# u1_heater_control.net
KiCad netlist of a schematic drawn in Altium Designer
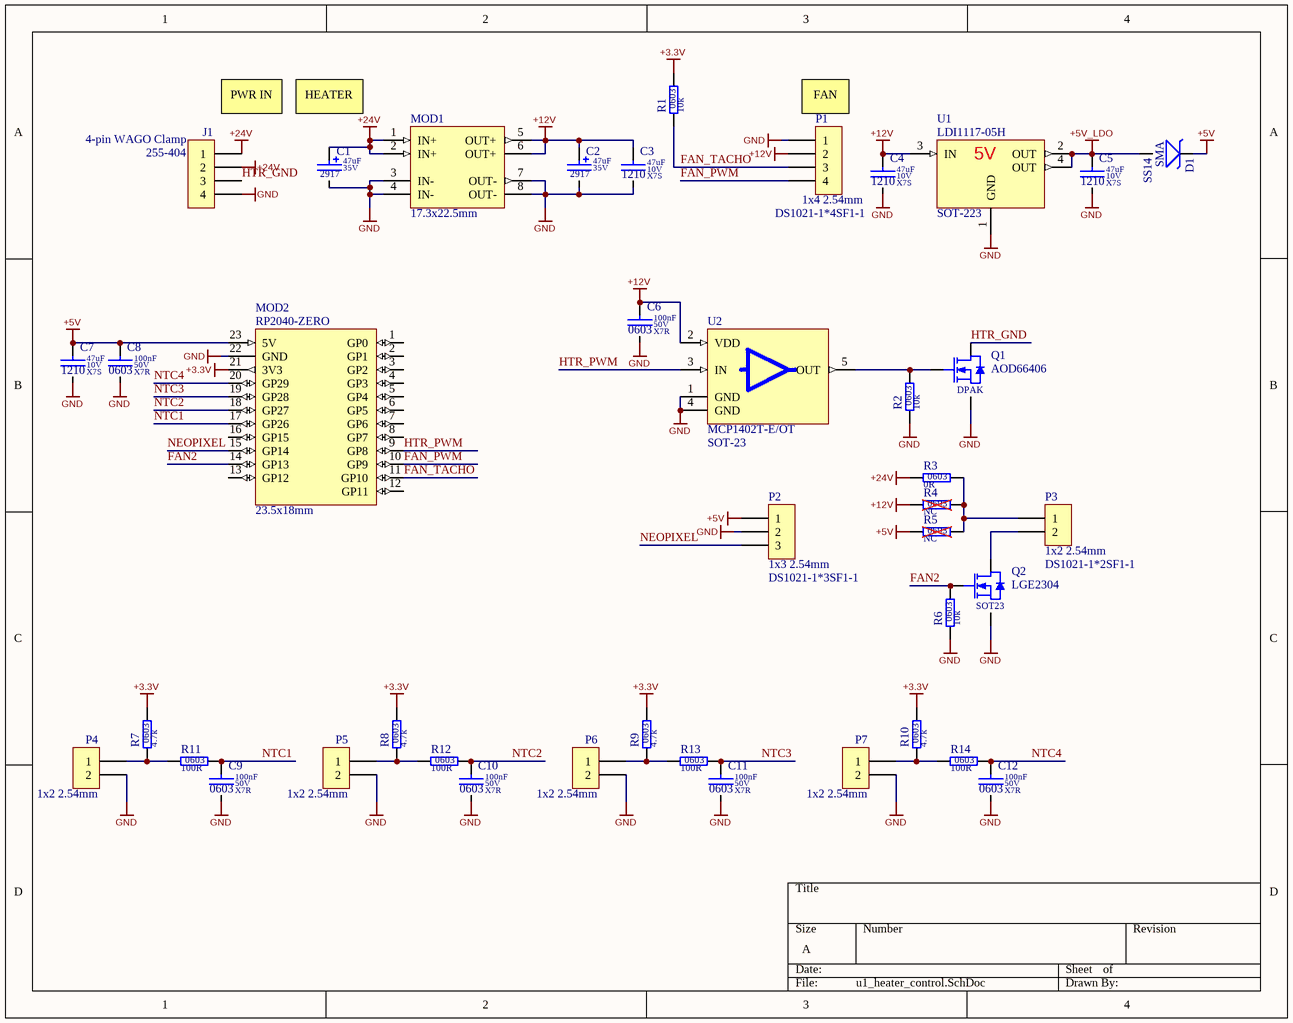
[diagram p0: u1_heater_control.SchDoc]

(export (version "E")
  (design (tool "Eeschema 10.0.6"))
  (components
    (comp (ref "C1")
      (value "47uF")
      (footprint "CT_2917_7343")
      (description "Capacitor")
      (fields
        (field (name "SCH_FOOTPRINT") "2917")
        (field (name "VOLTAGE") "35V")
        (field (name "PART NUMBER") "CT_47uF_35V_TA2O5_2917_20_T541")
        (field (name "MANUFACTURER") "Kemet")
      )
      (libsource (lib "Library") (part "CT"))
    )
    (comp (ref "C2")
      (value "47uF")
      (footprint "CT_2917_7343")
      (description "Capacitor")
      (fields
        (field (name "SCH_FOOTPRINT") "2917")
        (field (name "VOLTAGE") "35V")
        (field (name "PART NUMBER") "CT_47uF_35V_TA2O5_2917_20_T541")
        (field (name "MANUFACTURER") "Kemet")
      )
      (libsource (lib "Library") (part "CT"))
    )
    (comp (ref "C3")
      (value "47uF")
      (footprint "C_1210_3225")
      (description "Capacitor")
      (fields
        (field (name "DIELECTRIC") "X7S")
        (field (name "VOLTAGE") "10V")
        (field (name "SCH_FOOTPRINT") "1210")
        (field (name "PART NUMBER") "C_47uF_10V_X7S_1210_10_AECQ1")
        (field (name "MANUFACTURER") "Murata")
      )
      (libsource (lib "Library") (part "C"))
    )
    (comp (ref "C4")
      (value "47uF")
      (footprint "C_1210_3225")
      (description "Capacitor")
      (fields
        (field (name "DIELECTRIC") "X7S")
        (field (name "VOLTAGE") "10V")
        (field (name "SCH_FOOTPRINT") "1210")
        (field (name "PART NUMBER") "C_47uF_10V_X7S_1210_10_AECQ1")
        (field (name "MANUFACTURER") "Murata")
      )
      (libsource (lib "Library") (part "C"))
    )
    (comp (ref "C5")
      (value "47uF")
      (footprint "C_1210_3225")
      (description "Capacitor")
      (fields
        (field (name "DIELECTRIC") "X7S")
        (field (name "VOLTAGE") "10V")
        (field (name "SCH_FOOTPRINT") "1210")
        (field (name "PART NUMBER") "C_47uF_10V_X7S_1210_10_AECQ1")
        (field (name "MANUFACTURER") "Murata")
      )
      (libsource (lib "Library") (part "C"))
    )
    (comp (ref "C6")
      (value "100nF")
      (footprint "C_0603_1608")
      (description "Capacitor")
      (fields
        (field (name "DIELECTRIC") "X7R")
        (field (name "VOLTAGE") "50V")
        (field (name "SCH_FOOTPRINT") "0603")
        (field (name "PART NUMBER") "C_100nF_50V_X7R_0603_5")
        (field (name "MANUFACTURER") "Samsung")
      )
      (libsource (lib "Library") (part "C"))
    )
    (comp (ref "C7")
      (value "47uF")
      (footprint "C_1210_3225")
      (description "Capacitor")
      (fields
        (field (name "DIELECTRIC") "X7S")
        (field (name "VOLTAGE") "10V")
        (field (name "SCH_FOOTPRINT") "1210")
        (field (name "PART NUMBER") "C_47uF_10V_X7S_1210_10_AECQ1")
        (field (name "MANUFACTURER") "Murata")
      )
      (libsource (lib "Library") (part "C"))
    )
    (comp (ref "C8")
      (value "100nF")
      (footprint "C_0603_1608")
      (description "Capacitor")
      (fields
        (field (name "DIELECTRIC") "X7R")
        (field (name "VOLTAGE") "50V")
        (field (name "SCH_FOOTPRINT") "0603")
        (field (name "PART NUMBER") "C_100nF_50V_X7R_0603_5")
        (field (name "MANUFACTURER") "Samsung")
      )
      (libsource (lib "Library") (part "C"))
    )
    (comp (ref "C9")
      (value "100nF")
      (footprint "C_0603_1608")
      (description "Capacitor")
      (fields
        (field (name "DIELECTRIC") "X7R")
        (field (name "VOLTAGE") "50V")
        (field (name "SCH_FOOTPRINT") "0603")
        (field (name "PART NUMBER") "C_100nF_50V_X7R_0603_5")
        (field (name "MANUFACTURER") "Samsung")
      )
      (libsource (lib "Library") (part "C"))
    )
    (comp (ref "C10")
      (value "100nF")
      (footprint "C_0603_1608")
      (description "Capacitor")
      (fields
        (field (name "DIELECTRIC") "X7R")
        (field (name "VOLTAGE") "50V")
        (field (name "SCH_FOOTPRINT") "0603")
        (field (name "PART NUMBER") "C_100nF_50V_X7R_0603_5")
        (field (name "MANUFACTURER") "Samsung")
      )
      (libsource (lib "Library") (part "C"))
    )
    (comp (ref "C11")
      (value "100nF")
      (footprint "C_0603_1608")
      (description "Capacitor")
      (fields
        (field (name "DIELECTRIC") "X7R")
        (field (name "VOLTAGE") "50V")
        (field (name "SCH_FOOTPRINT") "0603")
        (field (name "PART NUMBER") "C_100nF_50V_X7R_0603_5")
        (field (name "MANUFACTURER") "Samsung")
      )
      (libsource (lib "Library") (part "C"))
    )
    (comp (ref "C12")
      (value "100nF")
      (footprint "C_0603_1608")
      (description "Capacitor")
      (fields
        (field (name "DIELECTRIC") "X7R")
        (field (name "VOLTAGE") "50V")
        (field (name "SCH_FOOTPRINT") "0603")
        (field (name "PART NUMBER") "C_100nF_50V_X7R_0603_5")
        (field (name "MANUFACTURER") "Samsung")
      )
      (libsource (lib "Library") (part "C"))
    )
    (comp (ref "D1")
      (value "SS14")
      (footprint "SMA_DO-214AC")
      (fields
        (field (name "SCH_FOOTPRINT") "SMA")
        (field (name "PART NUMBER") "DS_SS14_1A_40V_SMA")
        (field (name "VOLTAGE") "40V")
        (field (name "MANUFACTURER") "ON Semiconductor")
      )
      (libsource (lib "Library") (part "DS"))
    )
    (comp (ref "J1")
      (value "255-404")
      (footprint "J_255-404")
      (description "Pin Header")
      (fields
        (field (name "SCH_FOOTPRINT") "4-pin WAGO Clamp")
        (field (name "PART NUMBER") "J_255-404")
        (field (name "MANUFACTURER") "Wago")
      )
      (libsource (lib "Library") (part "J_HEADER_1x4"))
    )
    (comp (ref "MOD1")
      (value "Low cost, Aliexpress-ready DC-DC buck converter using MP1584")
      (footprint "MOD_BUCK_MP1584")
      (fields (field (name "SCH_FOOTPRINT") "17.3x22.5mm") (field (name "PART NUMBER") "MOD_BUCK_MP1584"))
      (libsource (lib "Library") (part "MOD_BUCK_MP1584"))
    )
    (comp (ref "MOD2")
      (value "RP2040-ZERO")
      (footprint "MOD_RP2040-ZERO")
      (fields
        (field (name "SCH_FOOTPRINT") "23.5x18mm")
        (field (name "PART NUMBER") "MOD_RP2040-ZERO")
        (field (name "MANUFACTURER") "Waveshare")
        (field (name "Comment") "RP2040 module")
      )
      (libsource (lib "Library") (part "MOD_RP2040-ZERO"))
    )
    (comp (ref "P1")
      (value "DS1021-1*4SF1-1")
      (footprint "P_HEADER_1x4_2.54")
      (description "Pin Header")
      (fields
        (field (name "SCH_FOOTPRINT") "1x4 2.54mm")
        (field (name "PART NUMBER") "P_HEADER_1x4_2.54")
        (field (name "MANUFACTURER") "Connfly")
      )
      (libsource (lib "Library") (part "P_HEADER_1x4"))
    )
    (comp (ref "P2")
      (value "DS1021-1*3SF1-1")
      (footprint "P_HEADER_1x3_2.54")
      (description "Pin Header")
      (fields
        (field (name "SCH_FOOTPRINT") "1x3 2.54mm")
        (field (name "PART NUMBER") "P_HEADER_1x3_2.54")
        (field (name "MANUFACTURER") "Connfly")
      )
      (libsource (lib "Library") (part "P_HEADER_1x3"))
    )
    (comp (ref "P3")
      (value "DS1021-1*2SF1-1")
      (footprint "P_HEADER_1x2_2.54")
      (description "Pin Header")
      (fields
        (field (name "SCH_FOOTPRINT") "1x2 2.54mm")
        (field (name "PART NUMBER") "P_HEADER_1x2_2.54")
        (field (name "MANUFACTURER") "Connfly")
      )
      (libsource (lib "") (part "P_HEADER_1x2_1"))
    )
    (comp (ref "P4")
      (value "Goldpin")
      (footprint "P_HEADER_1x2_2.54")
      (description "Pin Header")
      (fields
        (field (name "SCH_FOOTPRINT") "1x2 2.54mm")
        (field (name "PART NUMBER") "P_HEADER_1x2_2.54")
        (field (name "MANUFACTURER") "Connfly")
      )
      (libsource (lib "Library") (part "P_HEADER_1x2"))
    )
    (comp (ref "P5")
      (value "Goldpin")
      (footprint "P_HEADER_1x2_2.54")
      (description "Pin Header")
      (fields
        (field (name "SCH_FOOTPRINT") "1x2 2.54mm")
        (field (name "PART NUMBER") "P_HEADER_1x2_2.54")
        (field (name "MANUFACTURER") "Connfly")
      )
      (libsource (lib "Library") (part "P_HEADER_1x2"))
    )
    (comp (ref "P6")
      (value "Goldpin")
      (footprint "P_HEADER_1x2_2.54")
      (description "Pin Header")
      (fields
        (field (name "SCH_FOOTPRINT") "1x2 2.54mm")
        (field (name "PART NUMBER") "P_HEADER_1x2_2.54")
        (field (name "MANUFACTURER") "Connfly")
      )
      (libsource (lib "Library") (part "P_HEADER_1x2"))
    )
    (comp (ref "P7")
      (value "Goldpin")
      (footprint "P_HEADER_1x2_2.54")
      (description "Pin Header")
      (fields
        (field (name "SCH_FOOTPRINT") "1x2 2.54mm")
        (field (name "PART NUMBER") "P_HEADER_1x2_2.54")
        (field (name "MANUFACTURER") "Connfly")
      )
      (libsource (lib "Library") (part "P_HEADER_1x2"))
    )
    (comp (ref "Q1")
      (value "AOD66406")
      (footprint "DPAK_TO252-3_SC63_M")
      (fields
        (field (name "SCH_FOOTPRINT") "DPAK")
        (field (name "PART NUMBER") "QN_AOD66406")
        (field (name "VOLTAGE") "40V")
        (field (name "MANUFACTURER") "Alpha&Omega Semiconductor")
      )
      (libsource (lib "Library") (part "QN_GDS"))
    )
    (comp (ref "Q2")
      (value "LGE2304")
      (footprint "SOT23_TO236_SC59")
      (fields
        (field (name "SCH_FOOTPRINT") "SOT23")
        (field (name "PART NUMBER") "QN_LGE2304")
        (field (name "VOLTAGE") "30V")
        (field (name "MANUFACTURER") "Luguang Electronic Technology")
      )
      (libsource (lib "Library") (part "QN_GSD"))
    )
    (comp (ref "R1")
      (value "10k")
      (footprint "R_0603_1608")
      (fields
        (field (name "SCH_FOOTPRINT") "0603")
        (field (name "PART NUMBER") "R_10k_0603_1_AECQ0")
        (field (name "VOLTAGE") "75V")
        (field (name "POWER") "100mW")
      )
      (libsource (lib "Library") (part "R"))
    )
    (comp (ref "R2")
      (value "10k")
      (footprint "R_0603_1608")
      (fields
        (field (name "SCH_FOOTPRINT") "0603")
        (field (name "PART NUMBER") "R_10k_0603_1_AECQ0")
        (field (name "VOLTAGE") "75V")
        (field (name "POWER") "100mW")
      )
      (libsource (lib "Library") (part "R"))
    )
    (comp (ref "R3")
      (value "0R")
      (footprint "R_0603_1608")
      (fields
        (field (name "SCH_FOOTPRINT") "0603")
        (field (name "PART NUMBER") "R_0R_0603_1")
        (field (name "VOLTAGE") "75V")
        (field (name "POWER") "100mW")
      )
      (libsource (lib "Library") (part "R"))
    )
    (comp (ref "R4")
      (value "NC")
      (footprint "R_NC_0603_1608")
      (fields
        (field (name "SCH_FOOTPRINT") "0603")
        (field (name "PART NUMBER") "R_GENERIC_0603")
        (field (name "Comment") "Resistor")
      )
      (libsource (lib "Library") (part "R_NC"))
    )
    (comp (ref "R5")
      (value "NC")
      (footprint "R_NC_0603_1608")
      (fields
        (field (name "SCH_FOOTPRINT") "0603")
        (field (name "PART NUMBER") "R_GENERIC_0603")
        (field (name "Comment") "Resistor")
      )
      (libsource (lib "Library") (part "R_NC"))
    )
    (comp (ref "R6")
      (value "10k")
      (footprint "R_0603_1608")
      (fields
        (field (name "SCH_FOOTPRINT") "0603")
        (field (name "PART NUMBER") "R_10k_0603_1_AECQ0")
        (field (name "VOLTAGE") "75V")
        (field (name "POWER") "100mW")
      )
      (libsource (lib "Library") (part "R"))
    )
    (comp (ref "R7")
      (value "4.7k")
      (footprint "R_0603_1608")
      (fields
        (field (name "SCH_FOOTPRINT") "0603")
        (field (name "PART NUMBER") "R_4.7k_0603_1")
        (field (name "VOLTAGE") "75V")
        (field (name "POWER") "100mW")
      )
      (libsource (lib "Library") (part "R"))
    )
    (comp (ref "R8")
      (value "4.7k")
      (footprint "R_0603_1608")
      (fields
        (field (name "SCH_FOOTPRINT") "0603")
        (field (name "PART NUMBER") "R_4.7k_0603_1")
        (field (name "VOLTAGE") "75V")
        (field (name "POWER") "100mW")
      )
      (libsource (lib "Library") (part "R"))
    )
    (comp (ref "R9")
      (value "4.7k")
      (footprint "R_0603_1608")
      (fields
        (field (name "SCH_FOOTPRINT") "0603")
        (field (name "PART NUMBER") "R_4.7k_0603_1")
        (field (name "VOLTAGE") "75V")
        (field (name "POWER") "100mW")
      )
      (libsource (lib "Library") (part "R"))
    )
    (comp (ref "R10")
      (value "4.7k")
      (footprint "R_0603_1608")
      (fields
        (field (name "SCH_FOOTPRINT") "0603")
        (field (name "PART NUMBER") "R_4.7k_0603_1")
        (field (name "VOLTAGE") "75V")
        (field (name "POWER") "100mW")
      )
      (libsource (lib "Library") (part "R"))
    )
    (comp (ref "R11")
      (value "100R")
      (footprint "R_0603_1608")
      (fields
        (field (name "SCH_FOOTPRINT") "0603")
        (field (name "PART NUMBER") "R_100R_0603_1")
        (field (name "VOLTAGE") "50V")
        (field (name "POWER") "100mW")
      )
      (libsource (lib "Library") (part "R"))
    )
    (comp (ref "R12")
      (value "100R")
      (footprint "R_0603_1608")
      (fields
        (field (name "SCH_FOOTPRINT") "0603")
        (field (name "PART NUMBER") "R_100R_0603_1")
        (field (name "VOLTAGE") "50V")
        (field (name "POWER") "100mW")
      )
      (libsource (lib "Library") (part "R"))
    )
    (comp (ref "R13")
      (value "100R")
      (footprint "R_0603_1608")
      (fields
        (field (name "SCH_FOOTPRINT") "0603")
        (field (name "PART NUMBER") "R_100R_0603_1")
        (field (name "VOLTAGE") "50V")
        (field (name "POWER") "100mW")
      )
      (libsource (lib "Library") (part "R"))
    )
    (comp (ref "R14")
      (value "100R")
      (footprint "R_0603_1608")
      (fields
        (field (name "SCH_FOOTPRINT") "0603")
        (field (name "PART NUMBER") "R_100R_0603_1")
        (field (name "VOLTAGE") "50V")
        (field (name "POWER") "100mW")
      )
      (libsource (lib "Library") (part "R"))
    )
    (comp (ref "U1")
      (value "LDI1117-05H")
      (footprint "SOT223_SC73")
      (description "typical configuration")
      (fields
        (field (name "SCH_FOOTPRINT") "SOT-223")
        (field (name "PART NUMBER") "VL_LDI1117-05H")
        (field (name "VOLTAGE") "5V")
      )
      (libsource (lib "Library") (part "VL_4pin_3_1_2,4"))
    )
    (comp (ref "U2")
      (value "MCP1402T-E/OT")
      (footprint "SOT23-5_SC74A_SOT753_M")
      (fields
        (field (name "SCH_FOOTPRINT") "SOT-23")
        (field (name "PART NUMBER") "U_MCP1402T-E/OT")
        (field (name "MANUFACTURER") "Microchip")
        (field (name "Comment") "Mosfet driver")
      )
      (libsource (lib "Library") (part "U_MCP1402"))
    )
  )
  (nets
    (net (code "1") (name "+3.3V") (class "Default")
      (node (ref "MOD2") (pin "21") (pinfunction "3V3_21") (pintype "output"))
      (node (ref "R1") (pin "2") (pinfunction "2_2") (pintype "passive"))
      (node (ref "R10") (pin "2") (pinfunction "2_2") (pintype "passive"))
      (node (ref "R7") (pin "2") (pinfunction "2_2") (pintype "passive"))
      (node (ref "R8") (pin "2") (pinfunction "2_2") (pintype "passive"))
      (node (ref "R9") (pin "2") (pinfunction "2_2") (pintype "passive"))
    )
    (net (code "2") (name "+5V") (class "Default")
      (node (ref "C7") (pin "1") (pinfunction "1_1") (pintype "passive"))
      (node (ref "C8") (pin "1") (pinfunction "1_1") (pintype "passive"))
      (node (ref "D1") (pin "1") (pintype "passive"))
      (node (ref "MOD2") (pin "23") (pinfunction "5V_23") (pintype "input"))
      (node (ref "P2") (pin "1") (pinfunction "1_1") (pintype "passive"))
      (node (ref "R5") (pin "1") (pinfunction "1_1") (pintype "passive"))
    )
    (net (code "3") (name "+5V_LDO") (class "Default")
      (node (ref "C5") (pin "1") (pinfunction "1_1") (pintype "passive"))
      (node (ref "D1") (pin "2") (pintype "passive"))
      (node (ref "U1") (pin "2") (pinfunction "OUT_2") (pintype "output"))
      (node (ref "U1") (pin "4") (pinfunction "OUT_4") (pintype "output"))
    )
    (net (code "4") (name "+12V") (class "Default")
      (node (ref "C2") (pin "1") (pinfunction "1_1") (pintype "passive"))
      (node (ref "C3") (pin "1") (pinfunction "1_1") (pintype "passive"))
      (node (ref "C4") (pin "1") (pinfunction "1_1") (pintype "passive"))
      (node (ref "C6") (pin "1") (pinfunction "1_1") (pintype "passive"))
      (node (ref "MOD1") (pin "5") (pinfunction "OUT+_5") (pintype "output"))
      (node (ref "MOD1") (pin "6") (pinfunction "OUT+_6") (pintype "passive"))
      (node (ref "P1") (pin "2") (pinfunction "2_2") (pintype "passive"))
      (node (ref "R4") (pin "1") (pinfunction "1_1") (pintype "passive"))
      (node (ref "U1") (pin "3") (pinfunction "IN_3") (pintype "input"))
      (node (ref "U2") (pin "2") (pinfunction "VDD_2") (pintype "input"))
    )
    (net (code "5") (name "+24V") (class "Default")
      (node (ref "C1") (pin "1") (pinfunction "1_1") (pintype "passive"))
      (node (ref "J1") (pin "1") (pinfunction "1_1") (pintype "passive"))
      (node (ref "J1") (pin "2") (pinfunction "2_2") (pintype "passive"))
      (node (ref "MOD1") (pin "1") (pinfunction "IN+_1") (pintype "input"))
      (node (ref "MOD1") (pin "2") (pinfunction "IN+_2") (pintype "input"))
      (node (ref "R3") (pin "1") (pinfunction "1_1") (pintype "passive"))
    )
    (net (code "6") (name "/FAN2") (class "Default")
      (node (ref "MOD2") (pin "14") (pinfunction "GP13_14") (pintype "bidirectional"))
      (node (ref "Q2") (pin "1") (pinfunction "G_1") (pintype "passive"))
      (node (ref "R6") (pin "2") (pinfunction "2_2") (pintype "passive"))
    )
    (net (code "7") (name "/FAN_PWM") (class "Default")
      (node (ref "MOD2") (pin "10") (pinfunction "GP9_10") (pintype "bidirectional"))
      (node (ref "P1") (pin "4") (pinfunction "4_4") (pintype "passive"))
    )
    (net (code "8") (name "/FAN_TACHO") (class "Default")
      (node (ref "MOD2") (pin "11") (pinfunction "GP10_11") (pintype "bidirectional"))
      (node (ref "P1") (pin "3") (pinfunction "3_3") (pintype "passive"))
      (node (ref "R1") (pin "1") (pinfunction "1_1") (pintype "passive"))
    )
    (net (code "9") (name "/HTR_GND") (class "Default")
      (node (ref "J1") (pin "3") (pinfunction "3_3") (pintype "passive"))
      (node (ref "Q1") (pin "2") (pinfunction "D_2") (pintype "passive"))
    )
    (net (code "10") (name "/HTR_PWM") (class "Default")
      (node (ref "MOD2") (pin "9") (pinfunction "GP8_9") (pintype "bidirectional"))
      (node (ref "U2") (pin "3") (pinfunction "IN_3") (pintype "input"))
    )
    (net (code "11") (name "/NEOPIXEL") (class "Default")
      (node (ref "MOD2") (pin "15") (pinfunction "GP14_15") (pintype "bidirectional"))
      (node (ref "P2") (pin "3") (pinfunction "3_3") (pintype "passive"))
    )
    (net (code "12") (name "/NTC1") (class "Default")
      (node (ref "C9") (pin "1") (pinfunction "1_1") (pintype "passive"))
      (node (ref "MOD2") (pin "17") (pinfunction "GP26_17") (pintype "bidirectional"))
      (node (ref "R11") (pin "2") (pinfunction "2_2") (pintype "passive"))
    )
    (net (code "13") (name "/NTC2") (class "Default")
      (node (ref "C10") (pin "1") (pinfunction "1_1") (pintype "passive"))
      (node (ref "MOD2") (pin "18") (pinfunction "GP27_18") (pintype "bidirectional"))
      (node (ref "R12") (pin "2") (pinfunction "2_2") (pintype "passive"))
    )
    (net (code "14") (name "/NTC3") (class "Default")
      (node (ref "C11") (pin "1") (pinfunction "1_1") (pintype "passive"))
      (node (ref "MOD2") (pin "19") (pinfunction "GP28_19") (pintype "bidirectional"))
      (node (ref "R13") (pin "2") (pinfunction "2_2") (pintype "passive"))
    )
    (net (code "15") (name "/NTC4") (class "Default")
      (node (ref "C12") (pin "1") (pinfunction "1_1") (pintype "passive"))
      (node (ref "MOD2") (pin "20") (pinfunction "GP29_20") (pintype "bidirectional"))
      (node (ref "R14") (pin "2") (pinfunction "2_2") (pintype "passive"))
    )
    (net (code "16") (name "GND") (class "Default")
      (node (ref "C1") (pin "2") (pinfunction "2_2") (pintype "passive"))
      (node (ref "C10") (pin "2") (pinfunction "2_2") (pintype "passive"))
      (node (ref "C11") (pin "2") (pinfunction "2_2") (pintype "passive"))
      (node (ref "C12") (pin "2") (pinfunction "2_2") (pintype "passive"))
      (node (ref "C2") (pin "2") (pinfunction "2_2") (pintype "passive"))
      (node (ref "C3") (pin "2") (pinfunction "2_2") (pintype "passive"))
      (node (ref "C4") (pin "2") (pinfunction "2_2") (pintype "passive"))
      (node (ref "C5") (pin "2") (pinfunction "2_2") (pintype "passive"))
      (node (ref "C6") (pin "2") (pinfunction "2_2") (pintype "passive"))
      (node (ref "C7") (pin "2") (pinfunction "2_2") (pintype "passive"))
      (node (ref "C8") (pin "2") (pinfunction "2_2") (pintype "passive"))
      (node (ref "C9") (pin "2") (pinfunction "2_2") (pintype "passive"))
      (node (ref "J1") (pin "4") (pinfunction "4_4") (pintype "passive"))
      (node (ref "MOD1") (pin "3") (pinfunction "IN-_3") (pintype "power_in"))
      (node (ref "MOD1") (pin "4") (pinfunction "IN-_4") (pintype "power_in"))
      (node (ref "MOD1") (pin "7") (pinfunction "OUT-_7") (pintype "output"))
      (node (ref "MOD1") (pin "8") (pinfunction "OUT-_8") (pintype "passive"))
      (node (ref "MOD2") (pin "22") (pinfunction "GND_22") (pintype "power_in"))
      (node (ref "P1") (pin "1") (pinfunction "1_1") (pintype "passive"))
      (node (ref "P2") (pin "2") (pinfunction "2_2") (pintype "passive"))
      (node (ref "P4") (pin "2") (pinfunction "2_2") (pintype "passive"))
      (node (ref "P5") (pin "2") (pinfunction "2_2") (pintype "passive"))
      (node (ref "P6") (pin "2") (pinfunction "2_2") (pintype "passive"))
      (node (ref "P7") (pin "2") (pinfunction "2_2") (pintype "passive"))
      (node (ref "Q1") (pin "3") (pinfunction "S_3") (pintype "passive"))
      (node (ref "Q2") (pin "2") (pinfunction "S_2") (pintype "passive"))
      (node (ref "R2") (pin "1") (pinfunction "1_1") (pintype "passive"))
      (node (ref "R6") (pin "1") (pinfunction "1_1") (pintype "passive"))
      (node (ref "U1") (pin "1") (pinfunction "GND_1") (pintype "power_in"))
      (node (ref "U2") (pin "1") (pinfunction "GND_1") (pintype "power_in"))
      (node (ref "U2") (pin "4") (pinfunction "GND_4") (pintype "power_in"))
    )
    (net (code "17") (name "Net-(P3-Pad1)") (class "Default")
      (node (ref "P3") (pin "1") (pinfunction "1_1") (pintype "passive"))
      (node (ref "R3") (pin "2") (pinfunction "2_2") (pintype "passive"))
      (node (ref "R4") (pin "2") (pinfunction "2_2") (pintype "passive"))
      (node (ref "R5") (pin "2") (pinfunction "2_2") (pintype "passive"))
    )
    (net (code "18") (name "Net-(P4-Pad1)") (class "Default")
      (node (ref "P4") (pin "1") (pinfunction "1_1") (pintype "passive"))
      (node (ref "R11") (pin "1") (pinfunction "1_1") (pintype "passive"))
      (node (ref "R7") (pin "1") (pinfunction "1_1") (pintype "passive"))
    )
    (net (code "19") (name "Net-(P5-Pad1)") (class "Default")
      (node (ref "P5") (pin "1") (pinfunction "1_1") (pintype "passive"))
      (node (ref "R12") (pin "1") (pinfunction "1_1") (pintype "passive"))
      (node (ref "R8") (pin "1") (pinfunction "1_1") (pintype "passive"))
    )
    (net (code "20") (name "Net-(P6-Pad1)") (class "Default")
      (node (ref "P6") (pin "1") (pinfunction "1_1") (pintype "passive"))
      (node (ref "R13") (pin "1") (pinfunction "1_1") (pintype "passive"))
      (node (ref "R9") (pin "1") (pinfunction "1_1") (pintype "passive"))
    )
    (net (code "21") (name "Net-(P7-Pad1)") (class "Default")
      (node (ref "P7") (pin "1") (pinfunction "1_1") (pintype "passive"))
      (node (ref "R10") (pin "1") (pinfunction "1_1") (pintype "passive"))
      (node (ref "R14") (pin "1") (pinfunction "1_1") (pintype "passive"))
    )
    (net (code "22") (name "Net-(Q1-G)") (class "Default")
      (node (ref "Q1") (pin "1") (pinfunction "G_1") (pintype "passive"))
      (node (ref "R2") (pin "2") (pinfunction "2_2") (pintype "passive"))
      (node (ref "U2") (pin "5") (pinfunction "OUT_5") (pintype "output"))
    )
    (net (code "23") (name "Net-(Q2-D)") (class "Default")
      (node (ref "P3") (pin "2") (pinfunction "2_2") (pintype "passive"))
      (node (ref "Q2") (pin "3") (pinfunction "D_3") (pintype "passive"))
    )
    (net (code "24") (name "unconnected-(MOD2-GP0-Pad1)") (class "Default")
      (node (ref "MOD2") (pin "1") (pinfunction "GP0_1") (pintype "bidirectional"))
    )
    (net (code "25") (name "unconnected-(MOD2-GP1-Pad2)") (class "Default")
      (node (ref "MOD2") (pin "2") (pinfunction "GP1_2") (pintype "bidirectional"))
    )
    (net (code "26") (name "unconnected-(MOD2-GP2-Pad3)") (class "Default")
      (node (ref "MOD2") (pin "3") (pinfunction "GP2_3") (pintype "bidirectional"))
    )
    (net (code "27") (name "unconnected-(MOD2-GP3-Pad4)") (class "Default")
      (node (ref "MOD2") (pin "4") (pinfunction "GP3_4") (pintype "bidirectional"))
    )
    (net (code "28") (name "unconnected-(MOD2-GP4-Pad5)") (class "Default")
      (node (ref "MOD2") (pin "5") (pinfunction "GP4_5") (pintype "bidirectional"))
    )
    (net (code "29") (name "unconnected-(MOD2-GP5-Pad6)") (class "Default")
      (node (ref "MOD2") (pin "6") (pinfunction "GP5_6") (pintype "bidirectional"))
    )
    (net (code "30") (name "unconnected-(MOD2-GP6-Pad7)") (class "Default")
      (node (ref "MOD2") (pin "7") (pinfunction "GP6_7") (pintype "bidirectional"))
    )
    (net (code "31") (name "unconnected-(MOD2-GP7-Pad8)") (class "Default")
      (node (ref "MOD2") (pin "8") (pinfunction "GP7_8") (pintype "bidirectional"))
    )
    (net (code "32") (name "unconnected-(MOD2-GP11-Pad12)") (class "Default")
      (node (ref "MOD2") (pin "12") (pinfunction "GP11_12") (pintype "bidirectional"))
    )
    (net (code "33") (name "unconnected-(MOD2-GP12-Pad13)") (class "Default")
      (node (ref "MOD2") (pin "13") (pinfunction "GP12_13") (pintype "bidirectional"))
    )
    (net (code "34") (name "unconnected-(MOD2-GP15-Pad16)") (class "Default")
      (node (ref "MOD2") (pin "16") (pinfunction "GP15_16") (pintype "bidirectional"))
    )
  )
)
